# eps_bb1.net
KiCad netlist of a schematic drawn in Altium Designer
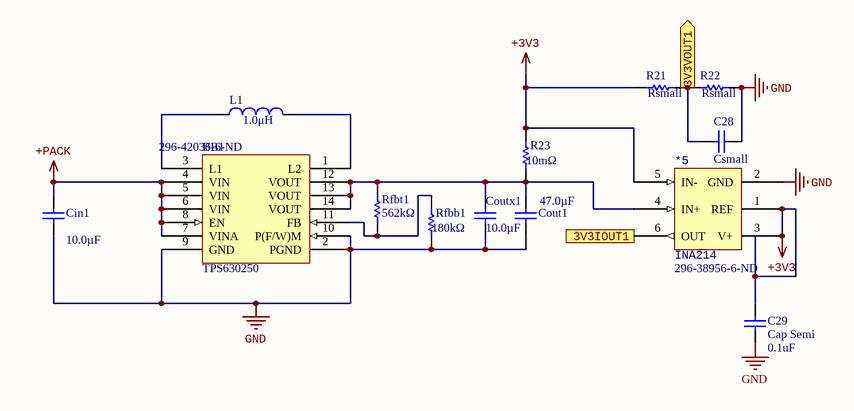
[diagram p0: eps_bb1.SchDoc]

(export (version "E")
  (design (tool "Eeschema 10.0.6"))
  (components
    (comp (ref "*5")
      (value "INA214")
      (footprint "SOT65P210X110-6N")
      (description "Current monitor")
      (fields (field (name "SUPPLIER PART NUMBER 1") "296-38956-6-ND"))
      (libsource (lib "heron-general") (part "INA214"))
    )
    (comp (ref "BB1")
      (value "TPS630250")
      (footprint "RNC0014A")
      (description "Buck-boost converter")
      (fields (field (name "SUPPLIER PART NUMBER 1") "296-42036-6-ND"))
      (libsource (lib "heron-general") (part "TPS630250"))
    )
    (comp (ref "C28")
      (value "Csmall")
      (footprint "1608[0603]")
      (description "Capacitor")
      (fields (field (name "Comment") "Cap") (field (name "PUBLISHER") "Altium Limited"))
      (libsource (lib "Miscellaneous Devices") (part "Cap"))
    )
    (comp (ref "C29")
      (value "Cap Semi")
      (footprint "1608[0603]")
      (description "Capacitor (Semiconductor SIM Model)")
      (fields (field (name "ALTIUM_VALUE") "0.1uF") (field (name "PUBLISHER") "Altium Limited"))
      (libsource (lib "Miscellaneous Devices") (part "Cap Semi"))
    )
    (comp (ref "Cin1")
      (value "10.0µF")
      (footprint "1608[0603]")
      (description "Capacitor")
      (fields (field (name "Comment") "Cap") (field (name "PUBLISHER") "Altium Limited"))
      (libsource (lib "Miscellaneous Devices") (part "Cap"))
    )
    (comp (ref "Cout1")
      (value "47.0µF")
      (footprint "1608[0603]")
      (description "Capacitor")
      (fields (field (name "Comment") "Cap") (field (name "PUBLISHER") "Altium Limited"))
      (libsource (lib "Miscellaneous Devices") (part "Cap"))
    )
    (comp (ref "Coutx1")
      (value "10.0µF")
      (footprint "1608[0603]")
      (description "Capacitor")
      (fields (field (name "Comment") "Cap") (field (name "PUBLISHER") "Altium Limited"))
      (libsource (lib "Miscellaneous Devices") (part "Cap"))
    )
    (comp (ref "L1")
      (value "1.0μH")
      (footprint "1608[0603]")
      (description "Inductor")
      (fields (field (name "PUBLISHER") "Altium Limited"))
      (libsource (lib "Miscellaneous Devices") (part "Inductor"))
    )
    (comp (ref "R21")
      (value "Rsmall")
      (footprint "1608[0603]")
      (description "Resistor")
      (fields (field (name "Comment") "Res1") (field (name "PUBLISHER") "Altium Limited"))
      (libsource (lib "Miscellaneous Devices") (part "Res1"))
    )
    (comp (ref "R22")
      (value "Rsmall")
      (footprint "1608[0603]")
      (description "Resistor")
      (fields (field (name "Comment") "Res1") (field (name "PUBLISHER") "Altium Limited"))
      (libsource (lib "Miscellaneous Devices") (part "Res1"))
    )
    (comp (ref "R23")
      (value "10mΩ")
      (footprint "1608[0603]")
      (description "Resistor")
      (fields (field (name "Comment") "Res1") (field (name "PUBLISHER") "Altium Limited"))
      (libsource (lib "Miscellaneous Devices") (part "Res1"))
    )
    (comp (ref "Rfbb1")
      (value "180kΩ")
      (footprint "1608[0603]")
      (description "Resistor")
      (fields (field (name "Comment") "Res1") (field (name "PUBLISHER") "Altium Limited"))
      (libsource (lib "Miscellaneous Devices") (part "Res1"))
    )
    (comp (ref "Rfbt1")
      (value "562kΩ")
      (footprint "1608[0603]")
      (description "Resistor")
      (fields (field (name "Comment") "Rfbt1") (field (name "PUBLISHER") "Altium Limited"))
      (libsource (lib "Miscellaneous Devices") (part "Res1"))
    )
  )
  (nets
    (net (code "1") (name "+3V3") (class "Default")
      (node (ref "*5") (pin "1") (pinfunction "REF_1") (pintype "passive"))
      (node (ref "*5") (pin "3") (pinfunction "V+_3") (pintype "power_in"))
      (node (ref "*5") (pin "5") (pinfunction "IN-_5") (pintype "input"))
      (node (ref "C29") (pin "2") (pinfunction "2_2") (pintype "passive"))
      (node (ref "R21") (pin "1") (pinfunction "1_1") (pintype "passive"))
      (node (ref "R23") (pin "2") (pinfunction "2_2") (pintype "passive"))
    )
    (net (code "2") (name "+PACK") (class "Default")
      (node (ref "BB1") (pin "4") (pinfunction "VIN_4") (pintype "power_in"))
      (node (ref "BB1") (pin "5") (pinfunction "VIN_5") (pintype "power_in"))
      (node (ref "BB1") (pin "6") (pinfunction "VIN_6") (pintype "power_in"))
      (node (ref "BB1") (pin "7") (pinfunction "VINA_7") (pintype "power_in"))
      (node (ref "BB1") (pin "8") (pinfunction "EN_8") (pintype "input"))
      (node (ref "Cin1") (pin "2") (pinfunction "2_2") (pintype "passive"))
    )
    (net (code "3") (name "/3V3IOUT1") (class "Default")
      (node (ref "*5") (pin "6") (pinfunction "OUT_6") (pintype "output"))
    )
    (net (code "4") (name "/3V3VOUT1") (class "Default")
      (node (ref "C28") (pin "2") (pinfunction "2_2") (pintype "passive"))
      (node (ref "R21") (pin "2") (pinfunction "2_2") (pintype "passive"))
      (node (ref "R22") (pin "1") (pinfunction "1_1") (pintype "passive"))
    )
    (net (code "5") (name "GND") (class "Default")
      (node (ref "*5") (pin "2") (pinfunction "GND_2") (pintype "power_in"))
      (node (ref "BB1") (pin "10") (pinfunction "P(F/W)M_10") (pintype "input"))
      (node (ref "BB1") (pin "2") (pinfunction "PGND_2") (pintype "power_in"))
      (node (ref "BB1") (pin "9") (pinfunction "GND_9") (pintype "power_in"))
      (node (ref "C28") (pin "1") (pinfunction "1_1") (pintype "passive"))
      (node (ref "C29") (pin "1") (pinfunction "1_1") (pintype "passive"))
      (node (ref "Cin1") (pin "1") (pinfunction "1_1") (pintype "passive"))
      (node (ref "Cout1") (pin "1") (pinfunction "1_1") (pintype "passive"))
      (node (ref "Coutx1") (pin "1") (pinfunction "1_1") (pintype "passive"))
      (node (ref "R22") (pin "2") (pinfunction "2_2") (pintype "passive"))
      (node (ref "Rfbb1") (pin "1") (pinfunction "1_1") (pintype "passive"))
    )
    (net (code "6") (name "Net-(*5-IN+)") (class "Default")
      (node (ref "*5") (pin "4") (pinfunction "IN+_4") (pintype "input"))
      (node (ref "BB1") (pin "12") (pinfunction "VOUT_12") (pintype "passive"))
      (node (ref "BB1") (pin "13") (pinfunction "VOUT_13") (pintype "passive"))
      (node (ref "BB1") (pin "14") (pinfunction "VOUT_14") (pintype "passive"))
      (node (ref "Cout1") (pin "2") (pinfunction "2_2") (pintype "passive"))
      (node (ref "Coutx1") (pin "2") (pinfunction "2_2") (pintype "passive"))
      (node (ref "R23") (pin "1") (pinfunction "1_1") (pintype "passive"))
      (node (ref "Rfbt1") (pin "1") (pinfunction "1_1") (pintype "passive"))
    )
    (net (code "7") (name "Net-(BB1-FB)") (class "Default")
      (node (ref "BB1") (pin "11") (pinfunction "FB_11") (pintype "input"))
      (node (ref "Rfbb1") (pin "2") (pinfunction "2_2") (pintype "passive"))
      (node (ref "Rfbt1") (pin "2") (pinfunction "2_2") (pintype "passive"))
    )
    (net (code "8") (name "Net-(BB1-L1)") (class "Default")
      (node (ref "BB1") (pin "3") (pinfunction "L1_3") (pintype "power_in"))
      (node (ref "L1") (pin "1") (pinfunction "1_1") (pintype "passive"))
    )
    (net (code "9") (name "Net-(BB1-L2)") (class "Default")
      (node (ref "BB1") (pin "1") (pinfunction "L2_1") (pintype "power_in"))
      (node (ref "L1") (pin "2") (pinfunction "2_2") (pintype "passive"))
    )
  )
)
